# greenhousectrl-latest-saturday.net
KiCad netlist of a schematic drawn in EAGLE
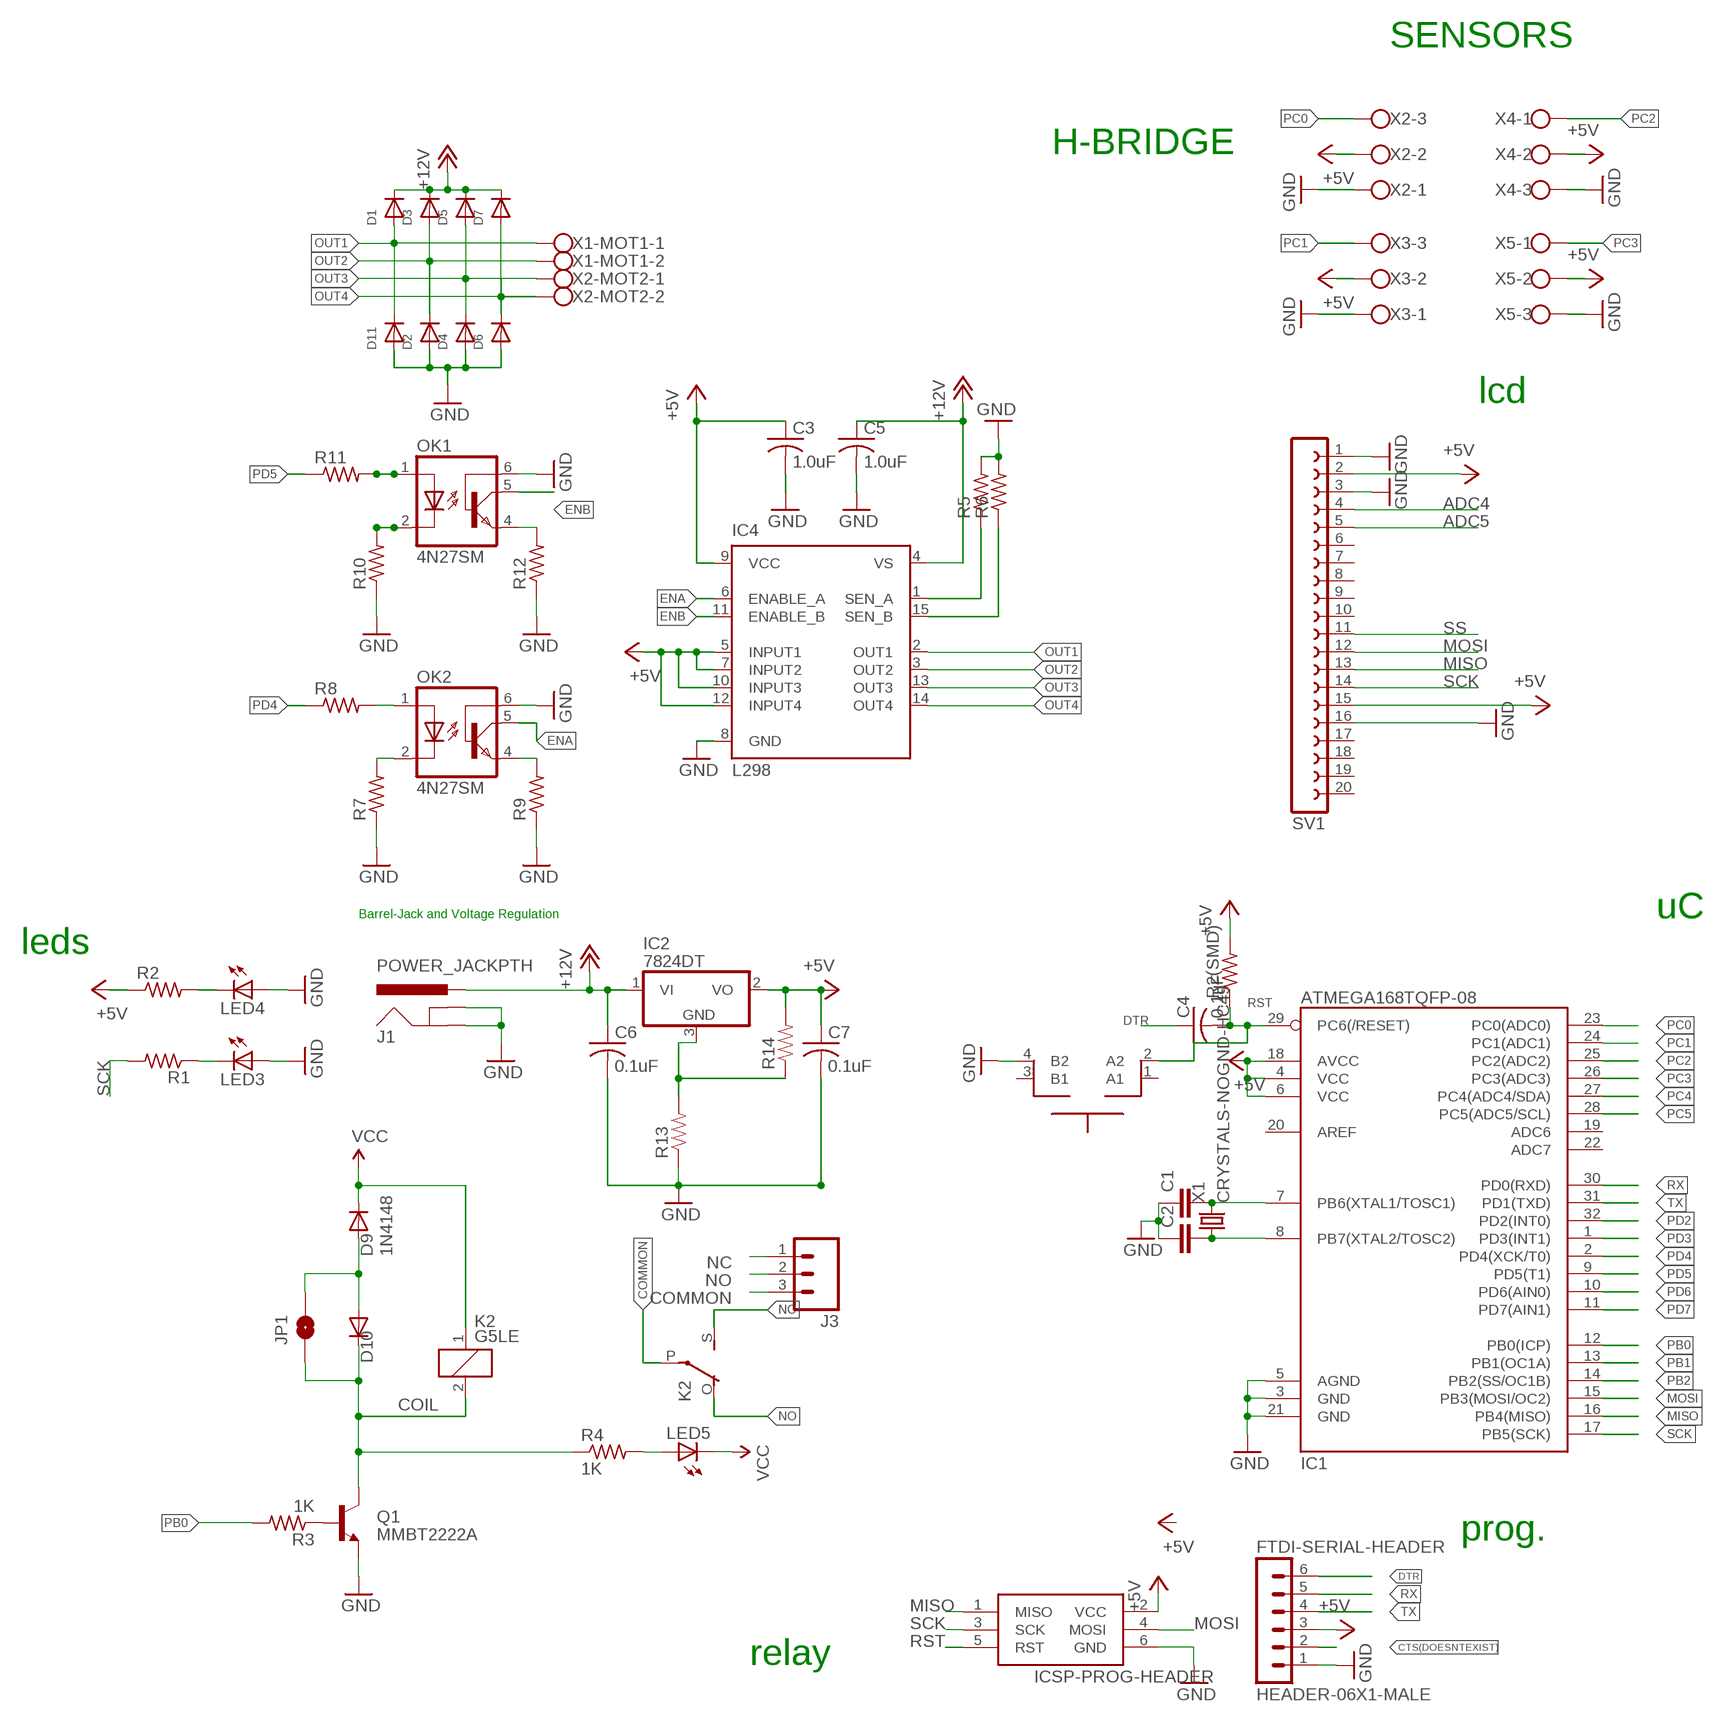
[diagram p0: schematic, sheet 1]

(export (version "E")
  (design (tool "Eeschema 10.0.6"))
  (components
    (comp (ref "C1")
      (value "C-EUC0805")
      (footprint "eagle-import:C0805")
      (libsource (lib "eagle-import") (part "C-EUC0805"))
    )
    (comp (ref "C2")
      (value "C-EUC0805")
      (footprint "eagle-import:C0805")
      (libsource (lib "eagle-import") (part "C-EUC0805"))
    )
    (comp (ref "C3")
      (value "1.0uF")
      (footprint "eagle-import:C0805")
      (libsource (lib "eagle-import") (part "C-USC0805"))
    )
    (comp (ref "C4")
      (value "0.1uF")
      (footprint "eagle-import:C0805")
      (libsource (lib "eagle-import") (part "C-USC0805"))
    )
    (comp (ref "C5")
      (value "1.0uF")
      (footprint "eagle-import:C0805")
      (libsource (lib "eagle-import") (part "C-USC0805"))
    )
    (comp (ref "C6")
      (value "0.1uF")
      (footprint "eagle-import:C0805")
      (libsource (lib "eagle-import") (part "C-USC0805"))
    )
    (comp (ref "C7")
      (value "0.1uF")
      (footprint "eagle-import:C0805")
      (libsource (lib "eagle-import") (part "C-USC0805"))
    )
    (comp (ref "D1")
      (value "DIODESOD-523")
      (footprint "eagle-import:SOD-523")
      (libsource (lib "eagle-import") (part "DIODESOD-523"))
    )
    (comp (ref "D2")
      (value "DIODESOD-523")
      (footprint "eagle-import:SOD-523")
      (libsource (lib "eagle-import") (part "DIODESOD-523"))
    )
    (comp (ref "D3")
      (value "DIODESOD-523")
      (footprint "eagle-import:SOD-523")
      (libsource (lib "eagle-import") (part "DIODESOD-523"))
    )
    (comp (ref "D4")
      (value "DIODESOD-523")
      (footprint "eagle-import:SOD-523")
      (libsource (lib "eagle-import") (part "DIODESOD-523"))
    )
    (comp (ref "D5")
      (value "DIODESOD-523")
      (footprint "eagle-import:SOD-523")
      (libsource (lib "eagle-import") (part "DIODESOD-523"))
    )
    (comp (ref "D6")
      (value "DIODESOD-523")
      (footprint "eagle-import:SOD-523")
      (libsource (lib "eagle-import") (part "DIODESOD-523"))
    )
    (comp (ref "D7")
      (value "DIODESOD-523")
      (footprint "eagle-import:SOD-523")
      (libsource (lib "eagle-import") (part "DIODESOD-523"))
    )
    (comp (ref "D9")
      (value "1N4148")
      (footprint "eagle-import:SOD-323F")
      (libsource (lib "eagle-import") (part "DIODESOD-323F"))
    )
    (comp (ref "D10")
      (value "Zener")
      (footprint "eagle-import:SOD-323F")
      (libsource (lib "eagle-import") (part "DIODESOD-323F"))
    )
    (comp (ref "D11")
      (value "DIODESOD-523")
      (footprint "eagle-import:SOD-523")
      (libsource (lib "eagle-import") (part "DIODESOD-523"))
    )
    (comp (ref "FTDI-SERIAL-HEADER")
      (value "HEADER-06X1-MALE")
      (footprint "eagle-import:06X1-PTH")
      (libsource (lib "eagle-import") (part "HEADER-06X1?-MALE"))
    )
    (comp (ref "IC1")
      (value "ATMEGA168TQFP-08")
      (footprint "eagle-import:TQFP32-08")
      (libsource (lib "eagle-import") (part "ATMEGA168TQFP-08"))
    )
    (comp (ref "IC2")
      (value "7824DT")
      (footprint "eagle-import:TO252")
      (libsource (lib "eagle-import") (part "78DT24"))
    )
    (comp (ref "IC4")
      (value "L298")
      (footprint "eagle-import:MULTIWATT-15")
      (fields (field (name "MPN") "L298N"))
      (libsource (lib "eagle-import") (part "L298"))
    )
    (comp (ref "ICSP-PROG-HEADER")
      (value "AVRISP-6")
      (footprint "eagle-import:AVRISP")
      (libsource (lib "eagle-import") (part "AVRISP-6"))
    )
    (comp (ref "J1")
      (value "POWER_JACKPTH")
      (footprint "eagle-import:POWER_JACK_PTH")
      (libsource (lib "eagle-import") (part "POWER_JACKPTH"))
    )
    (comp (ref "J3")
      (value "M03-SCREW-5MM")
      (footprint "eagle-import:SCREWTERMINAL-5MM-3")
      (libsource (lib "eagle-import") (part "M03-SCREW-5MM"))
    )
    (comp (ref "JP1")
      (value "JUMPER-PAD-2-NOYES_SILK")
      (footprint "eagle-import:PAD-JUMPER-2-NO_YES_SILK")
      (libsource (lib "eagle-import") (part "JUMPER-PAD-2-NOYES_SILK"))
    )
    (comp (ref "K2")
      (value "G5LE")
      (footprint "eagle-import:G5LE")
      (libsource (lib "eagle-import") (part "G5LE"))
    )
    (comp (ref "LED3")
      (value "LEDCHIP-LED0805")
      (footprint "eagle-import:CHIP-LED0805")
      (libsource (lib "eagle-import") (part "LEDCHIP-LED0805"))
    )
    (comp (ref "LED4")
      (value "LEDCHIP-LED0805")
      (footprint "eagle-import:CHIP-LED0805")
      (libsource (lib "eagle-import") (part "LEDCHIP-LED0805"))
    )
    (comp (ref "LED5")
      (value "LEDCHIP-LED0805")
      (footprint "eagle-import:CHIP-LED0805")
      (libsource (lib "eagle-import") (part "LEDCHIP-LED0805"))
    )
    (comp (ref "OK1")
      (value "4N27SM")
      (footprint "eagle-import:DIL6-SMD")
      (fields (field (name "MF") "FAIRCHILD SEMICONDUCTOR") (field (name "MPN") "4N27S-M"))
      (libsource (lib "eagle-import") (part "4N?MS27"))
    )
    (comp (ref "OK2")
      (value "4N27SM")
      (footprint "eagle-import:DIL6-SMD")
      (fields (field (name "MF") "FAIRCHILD SEMICONDUCTOR") (field (name "MPN") "4N27S-M"))
      (libsource (lib "eagle-import") (part "4N?MS27"))
    )
    (comp (ref "Q1")
      (value "MMBT2222A")
      (footprint "eagle-import:SOT23-3")
      (libsource (lib "eagle-import") (part "TRANSISTOR_NPNMMBT2222A"))
    )
    (comp (ref "R1")
      (value "R-US_M0805")
      (footprint "eagle-import:M0805")
      (libsource (lib "eagle-import") (part "R-US_M0805"))
    )
    (comp (ref "R2")
      (value "R-US_M0805")
      (footprint "eagle-import:M0805")
      (libsource (lib "eagle-import") (part "R-US_M0805"))
    )
    (comp (ref "R2(SMD)")
      (value "R-US_M0805")
      (footprint "eagle-import:M0805")
      (libsource (lib "eagle-import") (part "R-US_M0805"))
    )
    (comp (ref "R3")
      (value "1K")
      (footprint "eagle-import:M0805")
      (libsource (lib "eagle-import") (part "R-US_M0805"))
    )
    (comp (ref "R4")
      (value "1K")
      (footprint "eagle-import:M0805")
      (libsource (lib "eagle-import") (part "R-US_M0805"))
    )
    (comp (ref "R5")
      (value "R-US_M0805")
      (footprint "eagle-import:M0805")
      (libsource (lib "eagle-import") (part "R-US_M0805"))
    )
    (comp (ref "R6")
      (value "R-US_M0805")
      (footprint "eagle-import:M0805")
      (libsource (lib "eagle-import") (part "R-US_M0805"))
    )
    (comp (ref "R7")
      (value "R-US_M0805")
      (footprint "eagle-import:M0805")
      (libsource (lib "eagle-import") (part "R-US_M0805"))
    )
    (comp (ref "R8")
      (value "R-US_M0805")
      (footprint "eagle-import:M0805")
      (libsource (lib "eagle-import") (part "R-US_M0805"))
    )
    (comp (ref "R9")
      (value "R-US_M0805")
      (footprint "eagle-import:M0805")
      (libsource (lib "eagle-import") (part "R-US_M0805"))
    )
    (comp (ref "R10")
      (value "R-US_M0805")
      (footprint "eagle-import:M0805")
      (libsource (lib "eagle-import") (part "R-US_M0805"))
    )
    (comp (ref "R11")
      (value "R-US_M0805")
      (footprint "eagle-import:M0805")
      (libsource (lib "eagle-import") (part "R-US_M0805"))
    )
    (comp (ref "R12")
      (value "R-US_M0805")
      (footprint "eagle-import:M0805")
      (libsource (lib "eagle-import") (part "R-US_M0805"))
    )
    (comp (ref "R13")
      (value "RESISTOR0402")
      (footprint "eagle-import:0402-RES")
      (libsource (lib "eagle-import") (part "RESISTOR0402"))
    )
    (comp (ref "R14")
      (value "RESISTOR0402")
      (footprint "eagle-import:0402-RES")
      (libsource (lib "eagle-import") (part "RESISTOR0402"))
    )
    (comp (ref "SV1")
      (value "FE20-1")
      (footprint "eagle-import:FE20")
      (libsource (lib "eagle-import") (part "FE20-1"))
    )
    (comp (ref "SW2")
      (value "MOMENTARYBUTTON")
      (footprint "eagle-import:SPST_NO_SMD")
      (libsource (lib "eagle-import") (part "MOMENTARYBUTTON"))
    )
    (comp (ref "X1")
      (value "CRYSTALS-NOGND-HC49")
      (footprint "eagle-import:HC49")
      (libsource (lib "eagle-import") (part "CRYSTALS-NOGND-HC49"))
    )
    (comp (ref "X1-MOT1")
      (value "W237-102")
      (footprint "eagle-import:W237-102")
      (fields (field (name "MPN") "237-102"))
      (libsource (lib "eagle-import") (part "W237-102"))
    )
    (comp (ref "X2")
      (value "1X03_5MM_SCREW")
      (footprint "eagle-import:W237-103")
      (fields (field (name "MPN") "237-103"))
      (libsource (lib "eagle-import") (part "1X03_5MM_SCREW"))
    )
    (comp (ref "X2-MOT2")
      (value "W237-102")
      (footprint "eagle-import:W237-102")
      (fields (field (name "MPN") "237-102"))
      (libsource (lib "eagle-import") (part "W237-102"))
    )
    (comp (ref "X3")
      (value "1X03_5MM_SCREW")
      (footprint "eagle-import:W237-103")
      (fields (field (name "MPN") "237-103"))
      (libsource (lib "eagle-import") (part "1X03_5MM_SCREW"))
    )
    (comp (ref "X4")
      (value "1X03_5MM_SCREW")
      (footprint "eagle-import:W237-103")
      (fields (field (name "MPN") "237-103"))
      (libsource (lib "eagle-import") (part "1X03_5MM_SCREW"))
    )
    (comp (ref "X5")
      (value "1X03_5MM_SCREW")
      (footprint "eagle-import:W237-103")
      (fields (field (name "MPN") "237-103"))
      (libsource (lib "eagle-import") (part "1X03_5MM_SCREW"))
    )
  )
  (nets
    (net (code "1") (name "+5V") (class "Default")
      (node (ref "C3") (pin "1") (pinfunction "1_1") (pintype "passive"))
      (node (ref "C7") (pin "1") (pinfunction "1_1") (pintype "passive"))
      (node (ref "FTDI-SERIAL-HEADER") (pin "3") (pinfunction "3_3") (pintype "passive"))
      (node (ref "IC1") (pin "18") (pinfunction "AVCC_18") (pintype "bidirectional"))
      (node (ref "IC1") (pin "4") (pinfunction "VCC_4") (pintype "bidirectional"))
      (node (ref "IC1") (pin "6") (pinfunction "VCC_6") (pintype "bidirectional"))
      (node (ref "IC2") (pin "2") (pinfunction "VO_2") (pintype "passive"))
      (node (ref "IC4") (pin "10") (pinfunction "INPUT3_10") (pintype "input"))
      (node (ref "IC4") (pin "12") (pinfunction "INPUT4_12") (pintype "input"))
      (node (ref "IC4") (pin "5") (pinfunction "INPUT1_5") (pintype "input"))
      (node (ref "IC4") (pin "7") (pinfunction "INPUT2_7") (pintype "input"))
      (node (ref "IC4") (pin "9") (pinfunction "VCC_9") (pintype "power_in"))
      (node (ref "ICSP-PROG-HEADER") (pin "2") (pinfunction "VCC_2") (pintype "power_in"))
      (node (ref "R14") (pin "2") (pinfunction "2_2") (pintype "passive"))
      (node (ref "R2") (pin "1") (pinfunction "1_1") (pintype "passive"))
      (node (ref "R2(SMD)") (pin "2") (pinfunction "2_2") (pintype "passive"))
      (node (ref "SV1") (pin "15") (pinfunction "15_15") (pintype "passive"))
      (node (ref "SV1") (pin "2") (pinfunction "2_2") (pintype "passive"))
      (node (ref "X2") (pin "2") (pinfunction "KL_2") (pintype "passive"))
      (node (ref "X3") (pin "2") (pinfunction "KL_2") (pintype "passive"))
      (node (ref "X4") (pin "2") (pinfunction "KL_2") (pintype "passive"))
      (node (ref "X5") (pin "2") (pinfunction "KL_2") (pintype "passive"))
    )
    (net (code "2") (name "+12V") (class "Default")
      (node (ref "C5") (pin "1") (pinfunction "1_1") (pintype "passive"))
      (node (ref "C6") (pin "1") (pinfunction "1_1") (pintype "passive"))
      (node (ref "D1") (pin "K") (pinfunction "C_K") (pintype "passive"))
      (node (ref "D3") (pin "K") (pinfunction "C_K") (pintype "passive"))
      (node (ref "D5") (pin "K") (pinfunction "C_K") (pintype "passive"))
      (node (ref "D7") (pin "K") (pinfunction "C_K") (pintype "passive"))
      (node (ref "IC2") (pin "1") (pinfunction "VI_1") (pintype "input"))
      (node (ref "IC4") (pin "4") (pinfunction "VS_4") (pintype "power_in"))
      (node (ref "J1") (pin "PWR") (pinfunction "PWR_PWR") (pintype "bidirectional"))
    )
    (net (code "3") (name "/ADC4") (class "Default")
      (node (ref "SV1") (pin "4") (pinfunction "4_4") (pintype "passive"))
    )
    (net (code "4") (name "/ADC5") (class "Default")
      (node (ref "SV1") (pin "5") (pinfunction "5_5") (pintype "passive"))
    )
    (net (code "5") (name "/COIL") (class "Default")
      (node (ref "D10") (pin "C") (pinfunction "C_C") (pintype "passive"))
      (node (ref "JP1") (pin "1") (pinfunction "1_1") (pintype "passive"))
      (node (ref "K2") (pin "2") (pinfunction "2_2") (pintype "passive"))
      (node (ref "Q1") (pin "3") (pinfunction "C_3") (pintype "passive"))
      (node (ref "R4") (pin "1") (pinfunction "1_1") (pintype "passive"))
    )
    (net (code "6") (name "/RST") (class "Default")
      (node (ref "C4") (pin "2") (pinfunction "2_2") (pintype "passive"))
      (node (ref "IC1") (pin "29") (pinfunction "PC6(/RESET)_29") (pintype "bidirectional"))
      (node (ref "ICSP-PROG-HEADER") (pin "5") (pinfunction "RST_5") (pintype "output"))
      (node (ref "R2(SMD)") (pin "1") (pinfunction "1_1") (pintype "passive"))
      (node (ref "SW2") (pin "2") (pinfunction "A2_2") (pintype "bidirectional"))
    )
    (net (code "7") (name "/SS") (class "Default")
      (node (ref "SV1") (pin "11") (pinfunction "11_11") (pintype "passive"))
    )
    (net (code "8") (name "COMMON") (class "Default")
      (node (ref "J3") (pin "3") (pinfunction "3_3") (pintype "passive"))
      (node (ref "K2") (pin "P") (pinfunction "P_P") (pintype "passive"))
    )
    (net (code "9") (name "CTS(DOESNTEXIST)") (class "Default")
      (node (ref "FTDI-SERIAL-HEADER") (pin "2") (pinfunction "2_2") (pintype "passive"))
    )
    (net (code "10") (name "DTR") (class "Default")
      (node (ref "C4") (pin "1") (pinfunction "1_1") (pintype "passive"))
      (node (ref "FTDI-SERIAL-HEADER") (pin "6") (pinfunction "6_6") (pintype "passive"))
    )
    (net (code "11") (name "ENA") (class "Default")
      (node (ref "IC4") (pin "6") (pinfunction "ENABLE_A_6") (pintype "input"))
      (node (ref "OK2") (pin "5") (pinfunction "COL_5") (pintype "passive"))
    )
    (net (code "12") (name "ENB") (class "Default")
      (node (ref "IC4") (pin "11") (pinfunction "ENABLE_B_11") (pintype "input"))
      (node (ref "OK1") (pin "5") (pinfunction "COL_5") (pintype "passive"))
    )
    (net (code "13") (name "GND") (class "Default")
      (node (ref "C1") (pin "1") (pinfunction "1_1") (pintype "passive"))
      (node (ref "C2") (pin "1") (pinfunction "1_1") (pintype "passive"))
      (node (ref "C3") (pin "2") (pinfunction "2_2") (pintype "passive"))
      (node (ref "C5") (pin "2") (pinfunction "2_2") (pintype "passive"))
      (node (ref "C6") (pin "2") (pinfunction "2_2") (pintype "passive"))
      (node (ref "C7") (pin "2") (pinfunction "2_2") (pintype "passive"))
      (node (ref "D11") (pin "A") (pinfunction "A_A") (pintype "passive"))
      (node (ref "D2") (pin "A") (pinfunction "A_A") (pintype "passive"))
      (node (ref "D4") (pin "A") (pinfunction "A_A") (pintype "passive"))
      (node (ref "D6") (pin "A") (pinfunction "A_A") (pintype "passive"))
      (node (ref "FTDI-SERIAL-HEADER") (pin "1") (pinfunction "1_1") (pintype "passive"))
      (node (ref "IC1") (pin "21") (pinfunction "GND_21") (pintype "bidirectional"))
      (node (ref "IC1") (pin "3") (pinfunction "GND_3") (pintype "bidirectional"))
      (node (ref "IC1") (pin "5") (pinfunction "AGND_5") (pintype "bidirectional"))
      (node (ref "IC4") (pin "8") (pinfunction "GND_8") (pintype "power_in"))
      (node (ref "ICSP-PROG-HEADER") (pin "6") (pinfunction "GND_6") (pintype "power_in"))
      (node (ref "J1") (pin "GND") (pinfunction "GND_GND") (pintype "bidirectional"))
      (node (ref "J1") (pin "GNDBREAK") (pinfunction "GNDBREAK_GNDBREAK") (pintype "bidirectional"))
      (node (ref "LED3") (pin "A") (pinfunction "A_A") (pintype "passive"))
      (node (ref "LED4") (pin "A") (pinfunction "A_A") (pintype "passive"))
      (node (ref "OK1") (pin "6") (pinfunction "BAS_6") (pintype "passive"))
      (node (ref "OK2") (pin "6") (pinfunction "BAS_6") (pintype "passive"))
      (node (ref "Q1") (pin "2") (pinfunction "E_2") (pintype "passive"))
      (node (ref "R10") (pin "1") (pinfunction "1_1") (pintype "passive"))
      (node (ref "R12") (pin "1") (pinfunction "1_1") (pintype "passive"))
      (node (ref "R13") (pin "1") (pinfunction "1_1") (pintype "passive"))
      (node (ref "R5") (pin "2") (pinfunction "2_2") (pintype "passive"))
      (node (ref "R6") (pin "2") (pinfunction "2_2") (pintype "passive"))
      (node (ref "R7") (pin "1") (pinfunction "1_1") (pintype "passive"))
      (node (ref "R9") (pin "1") (pinfunction "1_1") (pintype "passive"))
      (node (ref "SV1") (pin "1") (pinfunction "1_1") (pintype "passive"))
      (node (ref "SV1") (pin "16") (pinfunction "16_16") (pintype "passive"))
      (node (ref "SV1") (pin "3") (pinfunction "3_3") (pintype "passive"))
      (node (ref "SW2") (pin "4") (pinfunction "B2_4") (pintype "bidirectional"))
      (node (ref "X2") (pin "1") (pinfunction "KL_1") (pintype "passive"))
      (node (ref "X3") (pin "1") (pinfunction "KL_1") (pintype "passive"))
      (node (ref "X4") (pin "3") (pinfunction "KL_3") (pintype "passive"))
      (node (ref "X5") (pin "3") (pinfunction "KL_3") (pintype "passive"))
    )
    (net (code "14") (name "MISO") (class "Default")
      (node (ref "IC1") (pin "16") (pinfunction "PB4(MISO)_16") (pintype "bidirectional"))
      (node (ref "ICSP-PROG-HEADER") (pin "1") (pinfunction "MISO_1") (pintype "input"))
      (node (ref "SV1") (pin "13") (pinfunction "13_13") (pintype "passive"))
    )
    (net (code "15") (name "MOSI") (class "Default")
      (node (ref "IC1") (pin "15") (pinfunction "PB3(MOSI/OC2)_15") (pintype "bidirectional"))
      (node (ref "ICSP-PROG-HEADER") (pin "4") (pinfunction "MOSI_4") (pintype "output"))
      (node (ref "SV1") (pin "12") (pinfunction "12_12") (pintype "passive"))
    )
    (net (code "16") (name "NC") (class "Default")
      (node (ref "J3") (pin "1") (pinfunction "1_1") (pintype "passive"))
      (node (ref "K2") (pin "S") (pinfunction "S_S") (pintype "passive"))
    )
    (net (code "17") (name "NO") (class "Default")
      (node (ref "J3") (pin "2") (pinfunction "2_2") (pintype "passive"))
      (node (ref "K2") (pin "O") (pinfunction "O_O") (pintype "passive"))
    )
    (net (code "18") (name "Net-(D10-PadA)") (class "Default")
      (node (ref "D10") (pin "A") (pinfunction "A_A") (pintype "passive"))
      (node (ref "D9") (pin "A") (pinfunction "A_A") (pintype "passive"))
      (node (ref "JP1") (pin "2") (pinfunction "2_2") (pintype "passive"))
    )
    (net (code "19") (name "Net-(IC1-PB6(XTAL1{slash}TOSC1))") (class "Default")
      (node (ref "C1") (pin "2") (pinfunction "2_2") (pintype "passive"))
      (node (ref "IC1") (pin "7") (pinfunction "PB6(XTAL1/TOSC1)_7") (pintype "bidirectional"))
      (node (ref "X1") (pin "2") (pinfunction "2_2") (pintype "passive"))
    )
    (net (code "20") (name "Net-(IC1-PB7(XTAL2{slash}TOSC2))") (class "Default")
      (node (ref "C2") (pin "2") (pinfunction "2_2") (pintype "passive"))
      (node (ref "IC1") (pin "8") (pinfunction "PB7(XTAL2/TOSC2)_8") (pintype "bidirectional"))
      (node (ref "X1") (pin "1") (pinfunction "1_1") (pintype "passive"))
    )
    (net (code "21") (name "Net-(IC2-GND)") (class "Default")
      (node (ref "IC2") (pin "3") (pinfunction "GND_3") (pintype "passive"))
      (node (ref "R13") (pin "2") (pinfunction "2_2") (pintype "passive"))
      (node (ref "R14") (pin "1") (pinfunction "1_1") (pintype "passive"))
    )
    (net (code "22") (name "Net-(IC4-SEN_A)") (class "Default")
      (node (ref "IC4") (pin "1") (pinfunction "SEN_A_1") (pintype "input"))
      (node (ref "R5") (pin "1") (pinfunction "1_1") (pintype "passive"))
    )
    (net (code "23") (name "Net-(IC4-SEN_B)") (class "Default")
      (node (ref "IC4") (pin "15") (pinfunction "SEN_B_15") (pintype "input"))
      (node (ref "R6") (pin "1") (pinfunction "1_1") (pintype "passive"))
    )
    (net (code "24") (name "Net-(LED3-PadC)") (class "Default")
      (node (ref "LED3") (pin "C") (pinfunction "C_C") (pintype "passive"))
      (node (ref "R1") (pin "1") (pinfunction "1_1") (pintype "passive"))
    )
    (net (code "25") (name "Net-(LED4-PadC)") (class "Default")
      (node (ref "LED4") (pin "C") (pinfunction "C_C") (pintype "passive"))
      (node (ref "R2") (pin "2") (pinfunction "2_2") (pintype "passive"))
    )
    (net (code "26") (name "Net-(LED5-PadA)") (class "Default")
      (node (ref "LED5") (pin "A") (pinfunction "A_A") (pintype "passive"))
      (node (ref "R4") (pin "2") (pinfunction "2_2") (pintype "passive"))
    )
    (net (code "27") (name "Net-(OK1-A)") (class "Default")
      (node (ref "OK1") (pin "1") (pinfunction "A_1") (pintype "passive"))
      (node (ref "R11") (pin "2") (pinfunction "2_2") (pintype "passive"))
    )
    (net (code "28") (name "Net-(OK1-C)") (class "Default")
      (node (ref "OK1") (pin "2") (pinfunction "C_2") (pintype "passive"))
      (node (ref "R10") (pin "2") (pinfunction "2_2") (pintype "passive"))
    )
    (net (code "29") (name "Net-(OK1-EMI)") (class "Default")
      (node (ref "OK1") (pin "4") (pinfunction "EMI_4") (pintype "passive"))
      (node (ref "R12") (pin "2") (pinfunction "2_2") (pintype "passive"))
    )
    (net (code "30") (name "Net-(OK2-A)") (class "Default")
      (node (ref "OK2") (pin "1") (pinfunction "A_1") (pintype "passive"))
      (node (ref "R8") (pin "2") (pinfunction "2_2") (pintype "passive"))
    )
    (net (code "31") (name "Net-(OK2-C)") (class "Default")
      (node (ref "OK2") (pin "2") (pinfunction "C_2") (pintype "passive"))
      (node (ref "R7") (pin "2") (pinfunction "2_2") (pintype "passive"))
    )
    (net (code "32") (name "Net-(OK2-EMI)") (class "Default")
      (node (ref "OK2") (pin "4") (pinfunction "EMI_4") (pintype "passive"))
      (node (ref "R9") (pin "2") (pinfunction "2_2") (pintype "passive"))
    )
    (net (code "33") (name "Net-(Q1-B)") (class "Default")
      (node (ref "Q1") (pin "1") (pinfunction "B_1") (pintype "passive"))
      (node (ref "R3") (pin "1") (pinfunction "1_1") (pintype "passive"))
    )
    (net (code "34") (name "OUT1") (class "Default")
      (node (ref "D1") (pin "A") (pinfunction "A_A") (pintype "passive"))
      (node (ref "D11") (pin "K") (pinfunction "C_K") (pintype "passive"))
      (node (ref "IC4") (pin "2") (pinfunction "OUT1_2") (pintype "output"))
      (node (ref "X1-MOT1") (pin "1") (pinfunction "KL_1") (pintype "passive"))
    )
    (net (code "35") (name "OUT2") (class "Default")
      (node (ref "D2") (pin "K") (pinfunction "C_K") (pintype "passive"))
      (node (ref "D3") (pin "A") (pinfunction "A_A") (pintype "passive"))
      (node (ref "IC4") (pin "3") (pinfunction "OUT2_3") (pintype "output"))
      (node (ref "X1-MOT1") (pin "2") (pinfunction "KL_2") (pintype "passive"))
    )
    (net (code "36") (name "OUT3") (class "Default")
      (node (ref "D4") (pin "K") (pinfunction "C_K") (pintype "passive"))
      (node (ref "D5") (pin "A") (pinfunction "A_A") (pintype "passive"))
      (node (ref "IC4") (pin "13") (pinfunction "OUT3_13") (pintype "output"))
      (node (ref "X2-MOT2") (pin "1") (pinfunction "KL_1") (pintype "passive"))
    )
    (net (code "37") (name "OUT4") (class "Default")
      (node (ref "D6") (pin "K") (pinfunction "C_K") (pintype "passive"))
      (node (ref "D7") (pin "A") (pinfunction "A_A") (pintype "passive"))
      (node (ref "IC4") (pin "14") (pinfunction "OUT4_14") (pintype "output"))
      (node (ref "X2-MOT2") (pin "2") (pinfunction "KL_2") (pintype "passive"))
    )
    (net (code "38") (name "PB0") (class "Default")
      (node (ref "IC1") (pin "12") (pinfunction "PB0(ICP)_12") (pintype "bidirectional"))
      (node (ref "R3") (pin "2") (pinfunction "2_2") (pintype "passive"))
    )
    (net (code "39") (name "PB1") (class "Default")
      (node (ref "IC1") (pin "13") (pinfunction "PB1(OC1A)_13") (pintype "bidirectional"))
    )
    (net (code "40") (name "PB2") (class "Default")
      (node (ref "IC1") (pin "14") (pinfunction "PB2(SS/OC1B)_14") (pintype "bidirectional"))
    )
    (net (code "41") (name "PC0") (class "Default")
      (node (ref "IC1") (pin "23") (pinfunction "PC0(ADC0)_23") (pintype "bidirectional"))
      (node (ref "X2") (pin "3") (pinfunction "KL_3") (pintype "passive"))
    )
    (net (code "42") (name "PC1") (class "Default")
      (node (ref "IC1") (pin "24") (pinfunction "PC1(ADC1)_24") (pintype "bidirectional"))
      (node (ref "X3") (pin "3") (pinfunction "KL_3") (pintype "passive"))
    )
    (net (code "43") (name "PC2") (class "Default")
      (node (ref "IC1") (pin "25") (pinfunction "PC2(ADC2)_25") (pintype "bidirectional"))
      (node (ref "X4") (pin "1") (pinfunction "KL_1") (pintype "passive"))
    )
    (net (code "44") (name "PC3") (class "Default")
      (node (ref "IC1") (pin "26") (pinfunction "PC3(ADC3)_26") (pintype "bidirectional"))
      (node (ref "X5") (pin "1") (pinfunction "KL_1") (pintype "passive"))
    )
    (net (code "45") (name "PC4") (class "Default")
      (node (ref "IC1") (pin "27") (pinfunction "PC4(ADC4/SDA)_27") (pintype "bidirectional"))
    )
    (net (code "46") (name "PC5") (class "Default")
      (node (ref "IC1") (pin "28") (pinfunction "PC5(ADC5/SCL)_28") (pintype "bidirectional"))
    )
    (net (code "47") (name "PD2") (class "Default")
      (node (ref "IC1") (pin "32") (pinfunction "PD2(INT0)_32") (pintype "bidirectional"))
    )
    (net (code "48") (name "PD3") (class "Default")
      (node (ref "IC1") (pin "1") (pinfunction "PD3(INT1)_1") (pintype "bidirectional"))
    )
    (net (code "49") (name "PD4") (class "Default")
      (node (ref "IC1") (pin "2") (pinfunction "PD4(XCK/T0)_2") (pintype "bidirectional"))
      (node (ref "R8") (pin "1") (pinfunction "1_1") (pintype "passive"))
    )
    (net (code "50") (name "PD5") (class "Default")
      (node (ref "IC1") (pin "9") (pinfunction "PD5(T1)_9") (pintype "bidirectional"))
      (node (ref "R11") (pin "1") (pinfunction "1_1") (pintype "passive"))
    )
    (net (code "51") (name "PD6") (class "Default")
      (node (ref "IC1") (pin "10") (pinfunction "PD6(AIN0)_10") (pintype "bidirectional"))
    )
    (net (code "52") (name "PD7") (class "Default")
      (node (ref "IC1") (pin "11") (pinfunction "PD7(AIN1)_11") (pintype "bidirectional"))
    )
    (net (code "53") (name "RX") (class "Default")
      (node (ref "FTDI-SERIAL-HEADER") (pin "5") (pinfunction "5_5") (pintype "passive"))
      (node (ref "IC1") (pin "30") (pinfunction "PD0(RXD)_30") (pintype "bidirectional"))
    )
    (net (code "54") (name "SCK") (class "Default")
      (node (ref "IC1") (pin "17") (pinfunction "PB5(SCK)_17") (pintype "bidirectional"))
      (node (ref "ICSP-PROG-HEADER") (pin "3") (pinfunction "SCK_3") (pintype "output"))
      (node (ref "R1") (pin "2") (pinfunction "2_2") (pintype "passive"))
      (node (ref "SV1") (pin "14") (pinfunction "14_14") (pintype "passive"))
    )
    (net (code "55") (name "TX") (class "Default")
      (node (ref "FTDI-SERIAL-HEADER") (pin "4") (pinfunction "4_4") (pintype "passive"))
      (node (ref "IC1") (pin "31") (pinfunction "PD1(TXD)_31") (pintype "bidirectional"))
    )
    (net (code "56") (name "VCC") (class "Default")
      (node (ref "D9") (pin "C") (pinfunction "C_C") (pintype "passive"))
      (node (ref "K2") (pin "1") (pinfunction "1_1") (pintype "passive"))
      (node (ref "LED5") (pin "C") (pinfunction "C_C") (pintype "passive"))
    )
    (net (code "57") (name "unconnected-(IC1-ADC6-Pad19)") (class "Default")
      (node (ref "IC1") (pin "19") (pinfunction "ADC6_19") (pintype "bidirectional"))
    )
    (net (code "58") (name "unconnected-(IC1-ADC7-Pad22)") (class "Default")
      (node (ref "IC1") (pin "22") (pinfunction "ADC7_22") (pintype "bidirectional"))
    )
    (net (code "59") (name "unconnected-(IC1-AREF-Pad20)") (class "Default")
      (node (ref "IC1") (pin "20") (pinfunction "AREF_20") (pintype "bidirectional"))
    )
    (net (code "60") (name "unconnected-(SV1-Pad6)") (class "Default")
      (node (ref "SV1") (pin "6") (pinfunction "6_6") (pintype "passive"))
    )
    (net (code "61") (name "unconnected-(SV1-Pad7)") (class "Default")
      (node (ref "SV1") (pin "7") (pinfunction "7_7") (pintype "passive"))
    )
    (net (code "62") (name "unconnected-(SV1-Pad8)") (class "Default")
      (node (ref "SV1") (pin "8") (pinfunction "8_8") (pintype "passive"))
    )
    (net (code "63") (name "unconnected-(SV1-Pad9)") (class "Default")
      (node (ref "SV1") (pin "9") (pinfunction "9_9") (pintype "passive"))
    )
    (net (code "64") (name "unconnected-(SV1-Pad10)") (class "Default")
      (node (ref "SV1") (pin "10") (pinfunction "10_10") (pintype "passive"))
    )
    (net (code "65") (name "unconnected-(SV1-Pad17)") (class "Default")
      (node (ref "SV1") (pin "17") (pinfunction "17_17") (pintype "passive"))
    )
    (net (code "66") (name "unconnected-(SV1-Pad18)") (class "Default")
      (node (ref "SV1") (pin "18") (pinfunction "18_18") (pintype "passive"))
    )
    (net (code "67") (name "unconnected-(SV1-Pad19)") (class "Default")
      (node (ref "SV1") (pin "19") (pinfunction "19_19") (pintype "passive"))
    )
    (net (code "68") (name "unconnected-(SV1-Pad20)") (class "Default")
      (node (ref "SV1") (pin "20") (pinfunction "20_20") (pintype "passive"))
    )
    (net (code "69") (name "unconnected-(SW2-A1-Pad1)") (class "Default")
      (node (ref "SW2") (pin "1") (pinfunction "A1_1") (pintype "bidirectional"))
    )
    (net (code "70") (name "unconnected-(SW2-B1-Pad3)") (class "Default")
      (node (ref "SW2") (pin "3") (pinfunction "B1_3") (pintype "bidirectional"))
    )
  )
)
